# Main.net
KiCad netlist of a schematic drawn in Altium Designer
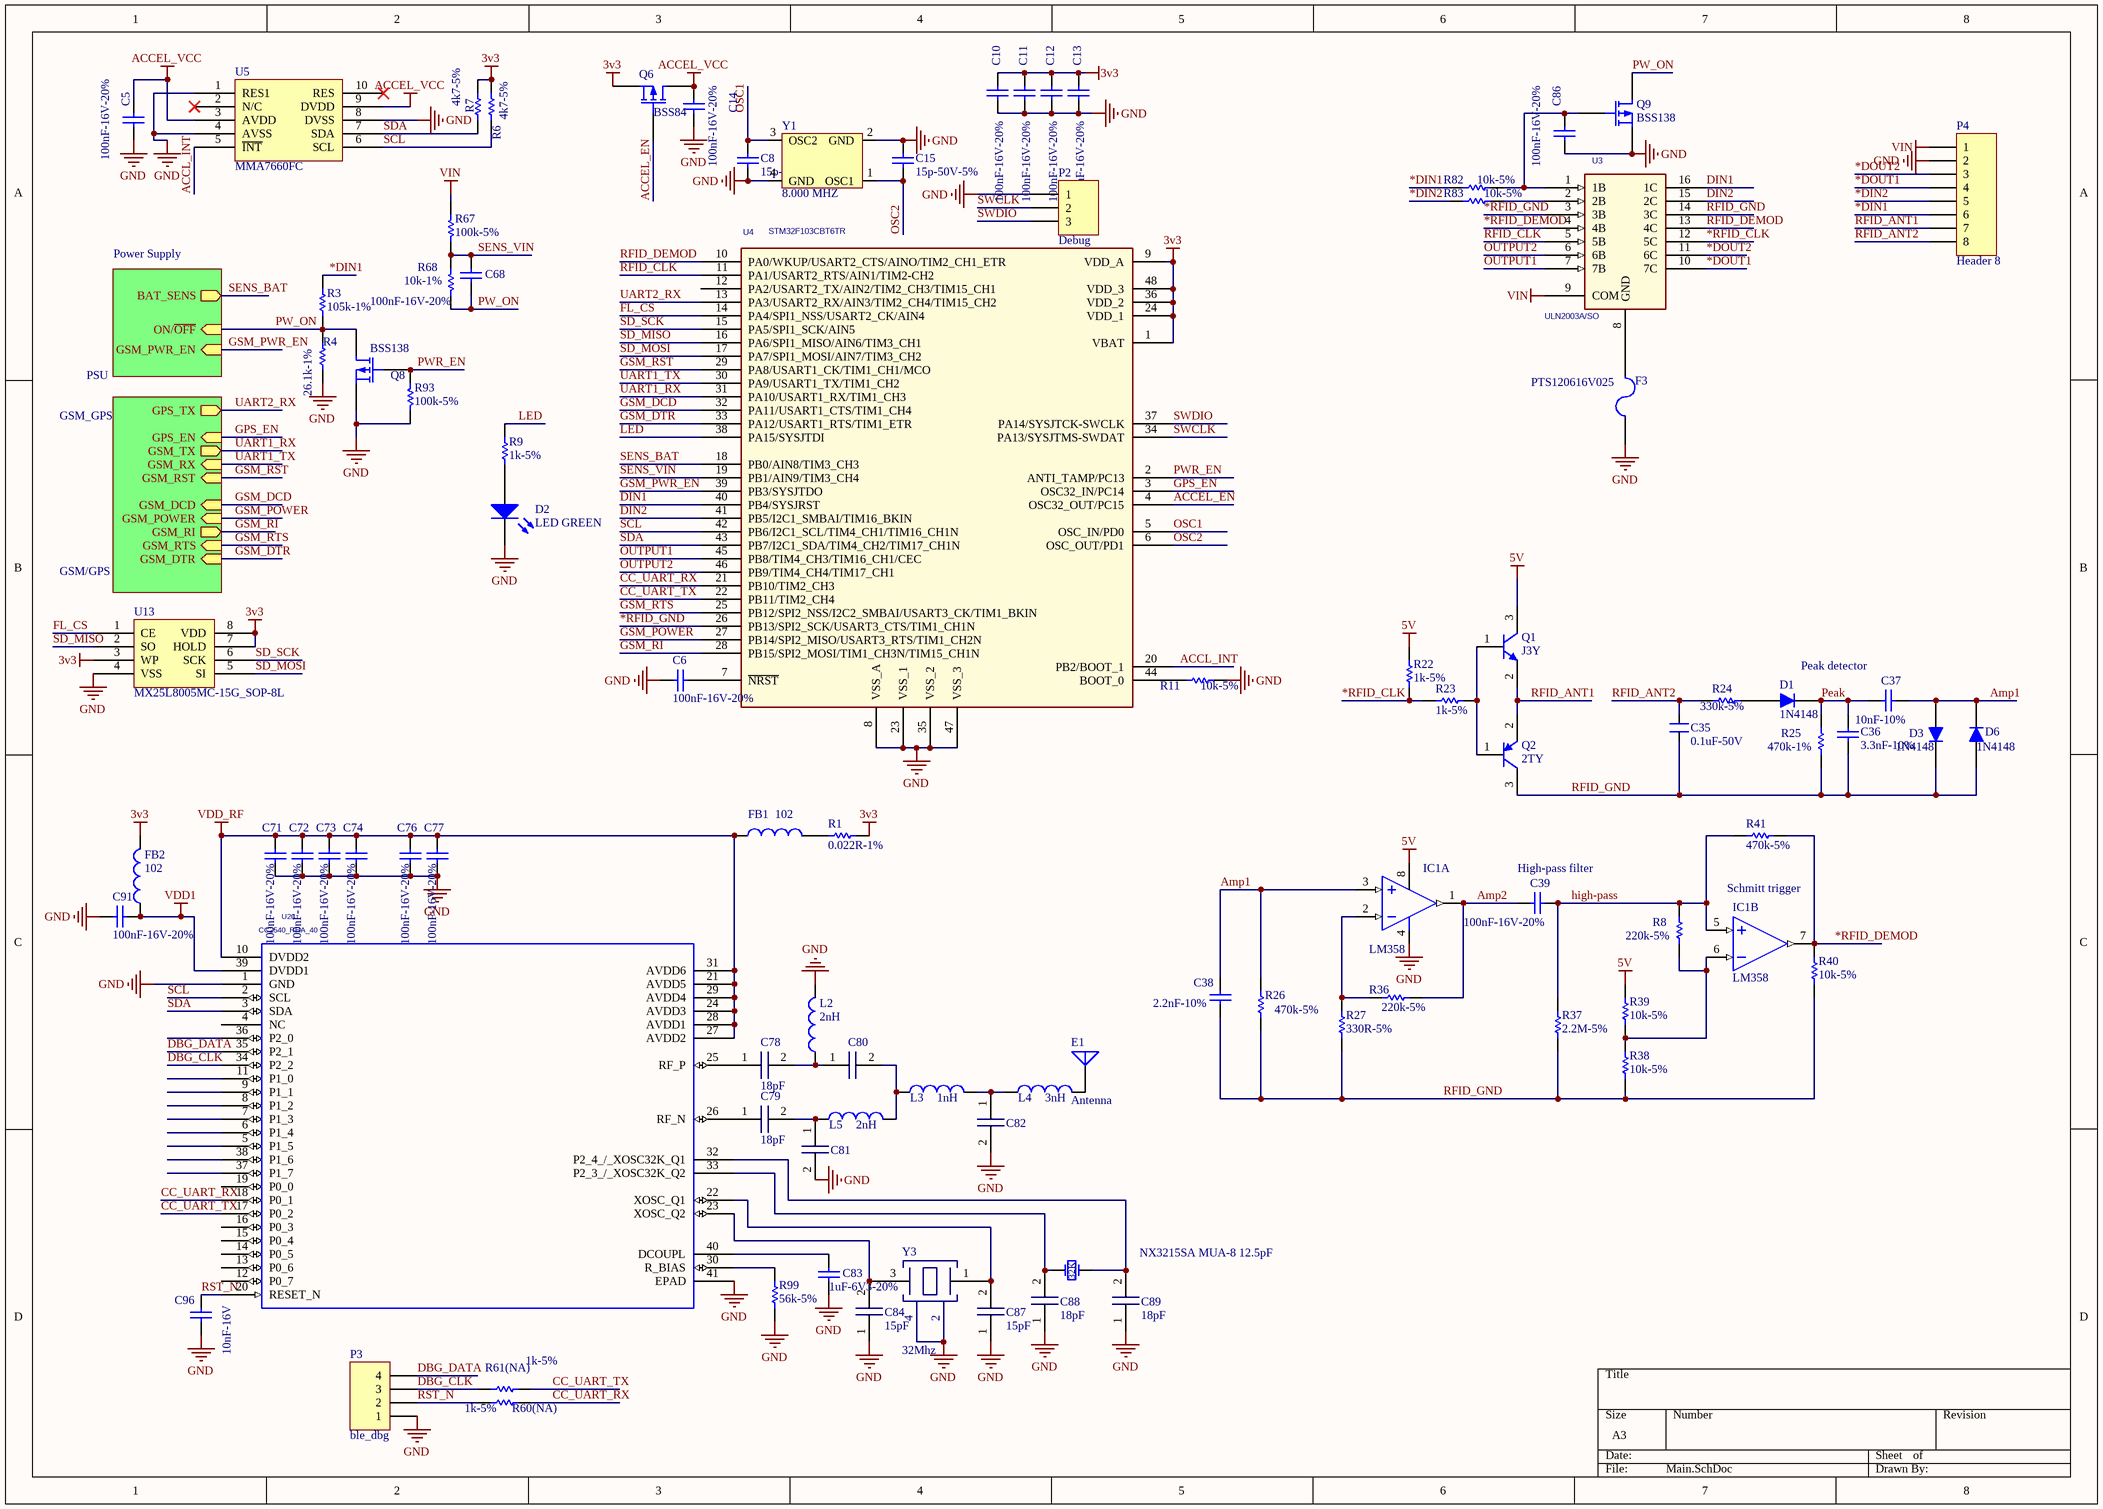
[diagram p0: Main.SchDoc]

(export (version "E")
  (design (tool "Eeschema 10.0.6"))
  (components
    (comp (ref "C5")
      (value "100nF-16V-20%")
      (footprint "C0402")
      (description "CAP CER 0.1UF 16V Y5V 0402")
      (fields
        (field (name "MANUFACTURER") "Yageo")
        (field (name "DIGI-KEY PART NUMBER") "311-1047-1-ND")
        (field (name "PUBLISHER") "Altium Limited")
      )
      (libsource (lib "Miscellaneous Devices") (part "Cap"))
    )
    (comp (ref "C6")
      (value "100nF-16V-20%")
      (footprint "C0402")
      (description "CAP CER 0.1UF 16V Y5V 0402")
      (fields
        (field (name "MANUFACTURER") "Yageo")
        (field (name "DIGI-KEY PART NUMBER") "311-1047-1-ND")
        (field (name "PUBLISHER") "Altium Limited")
      )
      (libsource (lib "Miscellaneous Devices") (part "Cap"))
    )
    (comp (ref "C8")
      (value "15p-50V-5%")
      (footprint "C0402")
      (description "CAP CER 15PF 50V 5% NPO 0402")
      (fields
        (field (name "MANUFACTURER") "Yageo")
        (field (name "DIGI-KEY PART NUMBER") "311-1017-1-ND")
        (field (name "PUBLISHER") "Altium Limited")
      )
      (libsource (lib "Miscellaneous Devices") (part "Cap"))
    )
    (comp (ref "C10")
      (value "100nF-16V-20%")
      (footprint "C0402")
      (description "CAP CER 0.1UF 16V Y5V 0402")
      (fields
        (field (name "MANUFACTURER") "Yageo")
        (field (name "DIGI-KEY PART NUMBER") "311-1047-1-ND")
        (field (name "PUBLISHER") "Altium Limited")
      )
      (libsource (lib "Miscellaneous Devices") (part "Cap"))
    )
    (comp (ref "C11")
      (value "100nF-16V-20%")
      (footprint "C0402")
      (description "CAP CER 0.1UF 16V Y5V 0402")
      (fields
        (field (name "MANUFACTURER") "Yageo")
        (field (name "DIGI-KEY PART NUMBER") "311-1047-1-ND")
        (field (name "PUBLISHER") "Altium Limited")
      )
      (libsource (lib "Miscellaneous Devices") (part "Cap"))
    )
    (comp (ref "C12")
      (value "100nF-16V-20%")
      (footprint "C0402")
      (description "CAP CER 0.1UF 16V Y5V 0402")
      (fields
        (field (name "MANUFACTURER") "Yageo")
        (field (name "DIGI-KEY PART NUMBER") "311-1047-1-ND")
        (field (name "PUBLISHER") "Altium Limited")
      )
      (libsource (lib "Miscellaneous Devices") (part "Cap"))
    )
    (comp (ref "C13")
      (value "100nF-16V-20%")
      (footprint "C0402")
      (description "CAP CER 0.1UF 16V Y5V 0402")
      (fields
        (field (name "MANUFACTURER") "Yageo")
        (field (name "DIGI-KEY PART NUMBER") "311-1047-1-ND")
        (field (name "PUBLISHER") "Altium Limited")
      )
      (libsource (lib "Miscellaneous Devices") (part "Cap"))
    )
    (comp (ref "C14")
      (value "100nF-16V-20%")
      (footprint "C0402")
      (description "CAP CER 0.1UF 16V Y5V 0402")
      (fields
        (field (name "MANUFACTURER") "Yageo")
        (field (name "DIGI-KEY PART NUMBER") "311-1047-1-ND")
        (field (name "PUBLISHER") "Altium Limited")
      )
      (libsource (lib "Miscellaneous Devices") (part "Cap"))
    )
    (comp (ref "C15")
      (value "15p-50V-5%")
      (footprint "C0402")
      (description "CAP CER 15PF 50V 5% NPO 0402")
      (fields
        (field (name "MANUFACTURER") "Yageo")
        (field (name "DIGI-KEY PART NUMBER") "311-1017-1-ND")
        (field (name "PUBLISHER") "Altium Limited")
      )
      (libsource (lib "Miscellaneous Devices") (part "Cap"))
    )
    (comp (ref "C35")
      (value "0.1uF-50V")
      (footprint "C0603")
      (description "CAP CER 0.1UF 50V Y5V 0603")
      (fields (field (name "DIGI-KEY PART NUMBER") "311-1343-2-ND") (field (name "MANUFACTURER") "Yageo"))
      (libsource (lib "syhaunguyen") (part "CN2"))
    )
    (comp (ref "C36")
      (value "3.3nF-10%")
      (footprint "C0402")
      (description "CAP CER 3300PF 50V 10% X7R 0402")
      (fields (field (name "DIGI-KEY PART NUMBER") "311-1034-2-ND") (field (name "MANUFACTURER") "Yageo"))
      (libsource (lib "Capacitor") (part "1nF-50V-C0805"))
    )
    (comp (ref "C37")
      (value "10nF-10%")
      (footprint "C0402")
      (description "Non-Polarized Capacitor")
      (fields (field (name "DIGI-KEY PART NUMBER") "CC0402KRX7R9BB103") (field (name "MANUFACTURER") "Yageo"))
      (libsource (lib "Capacitor") (part "10nF-50V-C0805"))
    )
    (comp (ref "C38")
      (value "2.2nF-10%")
      (footprint "C0402")
      (description "CAP CER 2200PF 50V 10% X7R 0402")
      (fields (field (name "DIGI-KEY PART NUMBER") "311-1037-2-ND") (field (name "MANUFACTURER") "Yageo"))
      (libsource (lib "Capacitor") (part "2.2nF-50V-C0805"))
    )
    (comp (ref "C39")
      (value "100nF-16V-20%")
      (footprint "C0402")
      (description "CAP CER 0.1UF 16V Y5V 0402")
      (fields
        (field (name "MANUFACTURER") "Yageo")
        (field (name "DIGI-KEY PART NUMBER") "311-1047-1-ND")
        (field (name "PUBLISHER") "Altium Limited")
      )
      (libsource (lib "Miscellaneous Devices") (part "Cap"))
    )
    (comp (ref "C68")
      (value "100nF-16V-20%")
      (footprint "C0402")
      (description "CAP CER 0.1UF 16V Y5V 0402")
      (fields
        (field (name "MANUFACTURER") "Yageo")
        (field (name "DIGI-KEY PART NUMBER") "311-1047-1-ND")
        (field (name "PUBLISHER") "Altium Limited")
      )
      (libsource (lib "Miscellaneous Devices") (part "Cap"))
    )
    (comp (ref "C71")
      (value "100nF-16V-20%")
      (footprint "C0402")
      (description "CAP CER 0.1UF 16V Y5V 0402")
      (fields
        (field (name "MANUFACTURER") "Yageo")
        (field (name "DIGI-KEY PART NUMBER") "311-1047-1-ND")
        (field (name "PUBLISHER") "Altium Limited")
      )
      (libsource (lib "Miscellaneous Devices") (part "Cap"))
    )
    (comp (ref "C72")
      (value "100nF-16V-20%")
      (footprint "C0402")
      (description "CAP CER 0.1UF 16V Y5V 0402")
      (fields
        (field (name "MANUFACTURER") "Yageo")
        (field (name "DIGI-KEY PART NUMBER") "311-1047-1-ND")
        (field (name "PUBLISHER") "Altium Limited")
      )
      (libsource (lib "Miscellaneous Devices") (part "Cap"))
    )
    (comp (ref "C73")
      (value "100nF-16V-20%")
      (footprint "C0402")
      (description "CAP CER 0.1UF 16V Y5V 0402")
      (fields
        (field (name "MANUFACTURER") "Yageo")
        (field (name "DIGI-KEY PART NUMBER") "311-1047-1-ND")
        (field (name "PUBLISHER") "Altium Limited")
      )
      (libsource (lib "Miscellaneous Devices") (part "Cap"))
    )
    (comp (ref "C74")
      (value "100nF-16V-20%")
      (footprint "C0402")
      (description "CAP CER 0.1UF 16V Y5V 0402")
      (fields
        (field (name "MANUFACTURER") "Yageo")
        (field (name "DIGI-KEY PART NUMBER") "311-1047-1-ND")
        (field (name "PUBLISHER") "Altium Limited")
      )
      (libsource (lib "Miscellaneous Devices") (part "Cap"))
    )
    (comp (ref "C76")
      (value "100nF-16V-20%")
      (footprint "C0402")
      (description "CAP CER 0.1UF 16V Y5V 0402")
      (fields
        (field (name "MANUFACTURER") "Yageo")
        (field (name "DIGI-KEY PART NUMBER") "311-1047-1-ND")
        (field (name "PUBLISHER") "Altium Limited")
      )
      (libsource (lib "Miscellaneous Devices") (part "Cap"))
    )
    (comp (ref "C77")
      (value "100nF-16V-20%")
      (footprint "C0402")
      (description "CAP CER 0.1UF 16V Y5V 0402")
      (fields
        (field (name "MANUFACTURER") "Yageo")
        (field (name "DIGI-KEY PART NUMBER") "311-1047-1-ND")
        (field (name "PUBLISHER") "Altium Limited")
      )
      (libsource (lib "Miscellaneous Devices") (part "Cap"))
    )
    (comp (ref "C78")
      (value "18pF")
      (footprint "C0402")
      (fields
        (field (name "MANUFACTURER") "Yageo")
        (field (name "DIGI-KEY PART NUMBER") "311-1018-1-ND")
        (field (name "MANUFACTURER PART NUMBER") "CC0402JRNPO9BN220")
      )
      (libsource (lib "Capacitor") (part "18pF"))
    )
    (comp (ref "C79")
      (value "18pF")
      (footprint "C0402")
      (fields
        (field (name "MANUFACTURER") "Yageo")
        (field (name "DIGI-KEY PART NUMBER") "311-1018-1-ND")
        (field (name "MANUFACTURER PART NUMBER") "CC0402JRNPO9BN220")
      )
      (libsource (lib "Capacitor") (part "18pF"))
    )
    (comp (ref "C80")
      (value "~")
      (footprint "C0402")
      (fields
        (field (name "DIGI-KEY PART NUMBER") "CC0402CRNPO9BN1R0-ND")
        (field (name "MANUFACTURER") "Yageo")
        (field (name "MANUFACTURER PART NUMBER") "CC0402CRNPO9BN1R0")
      )
      (libsource (lib "Capacitor") (part "1pF"))
    )
    (comp (ref "C81")
      (value "~")
      (footprint "C0402")
      (fields
        (field (name "DIGI-KEY PART NUMBER") "CC0402CRNPO9BN1R0-ND")
        (field (name "MANUFACTURER") "Yageo")
        (field (name "MANUFACTURER PART NUMBER") "CC0402CRNPO9BN1R0")
      )
      (libsource (lib "Capacitor") (part "1pF"))
    )
    (comp (ref "C82")
      (value "~")
      (footprint "C0402")
      (fields
        (field (name "DIGI-KEY PART NUMBER") "CC0402CRNPO9BN1R0-ND")
        (field (name "MANUFACTURER") "Yageo")
        (field (name "MANUFACTURER PART NUMBER") "CC0402CRNPO9BN1R0")
      )
      (libsource (lib "Capacitor") (part "1pF"))
    )
    (comp (ref "C83")
      (value "1uF-6V3-20%")
      (footprint "C0402")
      (description "CAP CER 1UF 6.3V Y5V 0402")
      (fields
        (field (name "MANUFACTURER") "Yageo")
        (field (name "DIGI-KEY PART NUMBER") "311-1377-2-ND")
        (field (name "PUBLISHER") "Altium Limited")
      )
      (libsource (lib "Miscellaneous Devices") (part "Cap"))
    )
    (comp (ref "C84")
      (value "15pF")
      (footprint "C0402")
      (fields
        (field (name "MANUFACTURER") "Yageo")
        (field (name "DIGI-KEY PART NUMBER") "311-1018-1-ND")
        (field (name "MANUFACTURER PART NUMBER") "CC0402JRNPO9BN220")
      )
      (libsource (lib "Capacitor") (part "15pF"))
    )
    (comp (ref "C86")
      (value "100nF-16V-20%")
      (footprint "C0402")
      (description "CAP CER 0.1UF 16V Y5V 0402")
      (fields
        (field (name "MANUFACTURER") "Yageo")
        (field (name "DIGI-KEY PART NUMBER") "311-1047-1-ND")
        (field (name "PUBLISHER") "Altium Limited")
      )
      (libsource (lib "Miscellaneous Devices") (part "Cap"))
    )
    (comp (ref "C87")
      (value "15pF")
      (footprint "C0402")
      (fields
        (field (name "MANUFACTURER") "Yageo")
        (field (name "DIGI-KEY PART NUMBER") "311-1018-1-ND")
        (field (name "MANUFACTURER PART NUMBER") "CC0402JRNPO9BN220")
      )
      (libsource (lib "Capacitor") (part "15pF"))
    )
    (comp (ref "C88")
      (value "18pF")
      (footprint "C0402")
      (fields
        (field (name "MANUFACTURER") "Yageo")
        (field (name "DIGI-KEY PART NUMBER") "311-1018-1-ND")
        (field (name "MANUFACTURER PART NUMBER") "CC0402JRNPO9BN220")
      )
      (libsource (lib "Capacitor") (part "18pF"))
    )
    (comp (ref "C89")
      (value "18pF")
      (footprint "C0402")
      (fields
        (field (name "MANUFACTURER") "Yageo")
        (field (name "DIGI-KEY PART NUMBER") "311-1018-1-ND")
        (field (name "MANUFACTURER PART NUMBER") "CC0402JRNPO9BN220")
      )
      (libsource (lib "Capacitor") (part "18pF"))
    )
    (comp (ref "C91")
      (value "100nF-16V-20%")
      (footprint "C0402")
      (description "CAP CER 0.1UF 16V Y5V 0402")
      (fields
        (field (name "MANUFACTURER") "Yageo")
        (field (name "DIGI-KEY PART NUMBER") "311-1047-1-ND")
        (field (name "PUBLISHER") "Altium Limited")
      )
      (libsource (lib "Miscellaneous Devices") (part "Cap"))
    )
    (comp (ref "C96")
      (value "10nF-16V")
      (footprint "C0402")
      (description "CAP CER 10000PF 16V 10% X7R 0402")
      (fields (field (name "DIGI-KEY PART NUMBER") "311-1042-2-ND") (field (name "MANUFACTURER") "Yageo"))
      (libsource (lib "Capacitor_0402") (part "10nF-16V-C0402-10%"))
    )
    (comp (ref "D1")
      (value "1N4148")
      (footprint "DO-213AA")
      (description "DIODE SMALL SIG 100V 0.2A ALF2")
      (fields
        (field (name "DIGI-KEY PART NUMBER") "568-1360-1-ND")
        (field (name "MANUFACTURER") "NXP Semiconductors")
      )
      (libsource (lib "Active Components") (part "1N4148"))
    )
    (comp (ref "D2")
      (value "LED GREEN")
      (footprint "LED0603-G")
      (description "LED GREEN CLEAR THIN 0603 SMD")
      (fields
        (field (name "DIGI-KEY PART NUMBER") "160-1446-2-ND")
        (field (name "MANUFACTURER") "Lite-On Inc")
        (field (name "PUBLISHER") "Altium Limited")
      )
      (libsource (lib "Miscellaneous Devices") (part "LED2"))
    )
    (comp (ref "D3")
      (value "1N4148")
      (footprint "DO-213AA")
      (description "DIODE SMALL SIG 100V 0.2A ALF2")
      (fields
        (field (name "DIGI-KEY PART NUMBER") "568-1360-1-ND")
        (field (name "MANUFACTURER") "NXP Semiconductors")
      )
      (libsource (lib "Active Components") (part "1N4148"))
    )
    (comp (ref "D6")
      (value "1N4148")
      (footprint "DO-213AA")
      (description "DIODE SMALL SIG 100V 0.2A ALF2")
      (fields
        (field (name "DIGI-KEY PART NUMBER") "568-1360-1-ND")
        (field (name "MANUFACTURER") "NXP Semiconductors")
      )
      (libsource (lib "Active Components") (part "1N4148"))
    )
    (comp (ref "E1")
      (value "Antenna")
      (footprint "A10192-ANTENOVA")
      (description "Generic Antenna")
      (fields (field (name "PUBLISHER") "Altium Limited"))
      (libsource (lib "Miscellaneous Devices") (part "Antenna"))
    )
    (comp (ref "F3")
      (value "PTS120616V025")
      (footprint "PTC1206")
      (description "PTC RESETTABLE SMD 1206 16V .25A")
      (fields
        (field (name "DIGI-KEY PART NUMBER") "283-3137-2-ND")
        (field (name "MANUFACTURER") "Cooper Bussmann")
        (field (name "PUBLISHER") "Altium Limited")
      )
      (libsource (lib "Miscellaneous Devices") (part "Fuse 2"))
    )
    (comp (ref "FB1")
      (value "102")
      (footprint "R0402")
      (description "Inductor")
      (fields
        (field (name "DIGI-KEY PART NUMBER") "490-1174-1-ND")
        (field (name "MANUFACTURER PART NUMBER") "LQW18AN27NJ00D")
        (field (name "PUBLISHER") "Altium Limited")
      )
      (libsource (lib "Miscellaneous Devices") (part "Inductor"))
    )
    (comp (ref "FB2")
      (value "102")
      (footprint "R0402")
      (description "Inductor")
      (fields
        (field (name "DIGI-KEY PART NUMBER") "490-1174-1-ND")
        (field (name "MANUFACTURER PART NUMBER") "LQW18AN27NJ00D")
        (field (name "PUBLISHER") "Altium Limited")
      )
      (libsource (lib "Miscellaneous Devices") (part "Inductor"))
    )
    (comp (ref "IC1")
      (value "LM358")
      (footprint "soic8")
      (description "Low-Power Dual Operational Amplifier")
      (libsource (lib "IC") (part "LM358"))
    )
    (comp (ref "L2")
      (value "2nH")
      (footprint "R0402")
      (description "Inductor")
      (fields
        (field (name "DIGI-KEY PART NUMBER") "490-1174-1-ND")
        (field (name "MANUFACTURER PART NUMBER") "LQW18AN27NJ00D")
        (field (name "PUBLISHER") "Altium Limited")
      )
      (libsource (lib "Miscellaneous Devices") (part "Inductor"))
    )
    (comp (ref "L3")
      (value "1nH")
      (footprint "R0402")
      (description "Inductor")
      (fields
        (field (name "DIGI-KEY PART NUMBER") "490-1174-1-ND")
        (field (name "MANUFACTURER PART NUMBER") "LQW18AN27NJ00D")
        (field (name "PUBLISHER") "Altium Limited")
      )
      (libsource (lib "Miscellaneous Devices") (part "Inductor"))
    )
    (comp (ref "L4")
      (value "3nH")
      (footprint "R0402")
      (description "Inductor")
      (fields
        (field (name "DIGI-KEY PART NUMBER") "490-1174-1-ND")
        (field (name "MANUFACTURER PART NUMBER") "LQW18AN27NJ00D")
        (field (name "PUBLISHER") "Altium Limited")
      )
      (libsource (lib "Miscellaneous Devices") (part "Inductor"))
    )
    (comp (ref "L5")
      (value "2nH")
      (footprint "R0402")
      (description "Inductor")
      (fields
        (field (name "DIGI-KEY PART NUMBER") "490-1174-1-ND")
        (field (name "MANUFACTURER PART NUMBER") "LQW18AN27NJ00D")
        (field (name "PUBLISHER") "Altium Limited")
      )
      (libsource (lib "Miscellaneous Devices") (part "Inductor"))
    )
    (comp (ref "P2")
      (value "Debug")
      (footprint "HEADER_1.27mm_3PIN")
      (description "NA")
      (fields (field (name "PUBLISHER") "Altium Limited"))
      (libsource (lib "Miscellaneous Connectors") (part "Header 3"))
    )
    (comp (ref "P3")
      (value "ble_dbg")
      (footprint "HEADER_1.27mm_4PIN")
      (description "Header, 4-Pin")
      (fields (field (name "PUBLISHER") "Altium Limited"))
      (libsource (lib "Miscellaneous Connectors") (part "Header 4"))
    )
    (comp (ref "P4")
      (value "Header 8")
      (footprint "HDR1X8")
      (description "Header, 8-Pin")
      (fields (field (name "PUBLISHER") "Altium Limited"))
      (libsource (lib "Miscellaneous Connectors") (part "Header 8"))
    )
    (comp (ref "Q1")
      (value "J3Y")
      (footprint "SOT23_123")
      (description "NPN Bipolar Transistor")
      (libsource (lib "Active Components") (part "NPN_123"))
    )
    (comp (ref "Q2")
      (value "2TY")
      (footprint "SOT23_123")
      (description "PNP Bipolar Transistor")
      (libsource (lib "Active Components") (part "PNP_123"))
    )
    (comp (ref "Q6")
      (value "BSS84")
      (footprint "SOT23-3")
      (description "MOSFET P-CH 50V 130MA SOT23-3")
      (fields
        (field (name "DIGI-KEY PART NUMBER") "BSS84-FDITR-ND")
        (field (name "MANUFACTURER") "Diodes Inc")
        (field (name "PUBLISHER") "Altium Limited")
      )
      (libsource (lib "") (part "MOSFET-P_1"))
    )
    (comp (ref "Q8")
      (value "BSS138")
      (footprint "SOT23-3")
      (description "MOSFET N-CH 50V 200MA SOT23-3")
      (fields
        (field (name "DIGI-KEY PART NUMBER") "BSS138-FDICT-ND")
        (field (name "MANUFACTURER") "Diodes Inc")
        (field (name "PUBLISHER") "Altium Limited")
      )
      (libsource (lib "Miscellaneous Devices") (part "MOSFET-P"))
    )
    (comp (ref "Q9")
      (value "BSS138")
      (footprint "SOT23-3")
      (description "MOSFET N-CH 50V 200MA SOT23-3")
      (fields
        (field (name "DIGI-KEY PART NUMBER") "BSS138-FDICT-ND")
        (field (name "MANUFACTURER") "Diodes Inc")
        (field (name "PUBLISHER") "Altium Limited")
      )
      (libsource (lib "Miscellaneous Devices") (part "MOSFET-P"))
    )
    (comp (ref "R1")
      (value "0.022R-1%")
      (footprint "R0402")
      (description "RES 0.022 OHM 1/4W 1% 0805 SMD")
      (fields (field (name "DIGI-KEY PART NUMBER") "311-0.022NSTR-ND") (field (name "MANUFACTURER") "Yageo"))
      (libsource (lib "All_Resistor") (part "0.022R-1%-R0805"))
    )
    (comp (ref "R3")
      (value "105k-1%")
      (footprint "R0402")
      (description "RES 105k OHM 1/4W 1% 0805 SMD")
      (fields (field (name "DIGI-KEY PART NUMBER") "311-105KCRTR-ND") (field (name "MANUFACTURER") "Yageo"))
      (libsource (lib "All_Resistor") (part "105k-1%-R0805"))
    )
    (comp (ref "R4")
      (value "26.1k-1%")
      (footprint "R0402")
      (description "RES 26.1k OHM 1/4W 1% 0805 SMD")
      (fields (field (name "DIGI-KEY PART NUMBER") "311-26.1KCRTR-ND") (field (name "MANUFACTURER") "Yageo"))
      (libsource (lib "All_Resistor") (part "26.1k-1%-R0805"))
    )
    (comp (ref "R6")
      (value "4k7-5%")
      (footprint "R0402")
      (description "RES 4.7K OHM 1/16W 5% 0402 SMD")
      (fields
        (field (name "DIGI-KEY PART NUMBER") "311-4.7KJRCT-ND")
        (field (name "MANUFACTURER") "Yageo")
        (field (name "PUBLISHER") "Altium Limited")
      )
      (libsource (lib "Miscellaneous Devices") (part "Res1"))
    )
    (comp (ref "R7")
      (value "4k7-5%")
      (footprint "R0402")
      (description "RES 4.7K OHM 1/16W 5% 0402 SMD")
      (fields
        (field (name "DIGI-KEY PART NUMBER") "311-4.7KJRCT-ND")
        (field (name "MANUFACTURER") "Yageo")
        (field (name "PUBLISHER") "Altium Limited")
      )
      (libsource (lib "Miscellaneous Devices") (part "Res1"))
    )
    (comp (ref "R8")
      (value "220k-5%")
      (footprint "R0402")
      (description "RES 220k OHM 1/8W 5% 0805 SMD")
      (fields (field (name "DIGI-KEY PART NUMBER") "311-220KARTR-ND") (field (name "MANUFACTURER") "Yageo"))
      (libsource (lib "Resistor") (part "220k-5%-R0805"))
    )
    (comp (ref "R9")
      (value "1k-5%")
      (footprint "R0402")
      (description "RES 1.0K OHM 1/16W 5% 0402 SMD")
      (fields
        (field (name "DIGI-KEY PART NUMBER") "311-1.0KJRCT-ND")
        (field (name "MANUFACTURER") "Yageo")
        (field (name "PUBLISHER") "Altium Limited")
      )
      (libsource (lib "Miscellaneous Devices") (part "Res1"))
    )
    (comp (ref "R11")
      (value "10k-5%")
      (footprint "R0402")
      (description "RES 10K OHM 1/16W 5% 0402 SMD")
      (fields
        (field (name "DIGI-KEY PART NUMBER") "311-10KJRCT-ND")
        (field (name "MANUFACTURER") "Yageo")
        (field (name "PUBLISHER") "Altium Limited")
      )
      (libsource (lib "Miscellaneous Devices") (part "Res1"))
    )
    (comp (ref "R22")
      (value "1k-5%")
      (footprint "R0402")
      (description "RES 1k OHM 1/8W 5% 0805 SMD")
      (fields (field (name "DIGI-KEY PART NUMBER") "311-1.0KARTR-ND") (field (name "MANUFACTURER") "Yageo"))
      (libsource (lib "All_Resistor") (part "1k-5%-R0805"))
    )
    (comp (ref "R23")
      (value "1k-5%")
      (footprint "R0402")
      (description "RES 1k OHM 1/8W 5% 0805 SMD")
      (fields (field (name "DIGI-KEY PART NUMBER") "311-1.0KARTR-ND") (field (name "MANUFACTURER") "Yageo"))
      (libsource (lib "All_Resistor") (part "1k-5%-R0805"))
    )
    (comp (ref "R24")
      (value "330k-5%")
      (footprint "R0402")
      (description "RES 330k OHM 1/8W 5% 0805 SMD")
      (fields (field (name "DIGI-KEY PART NUMBER") "311-330KARTR-ND") (field (name "MANUFACTURER") "Yageo"))
      (libsource (lib "Resistor") (part "330k-5%-R0805"))
    )
    (comp (ref "R25")
      (value "470k-1%")
      (footprint "R0402")
      (description "RES 470k OHM 1/4W 1% 0805 SMD")
      (fields (field (name "DIGI-KEY PART NUMBER") "311-470KCRTR-ND") (field (name "MANUFACTURER") "Yageo"))
      (libsource (lib "Resistor") (part "470k-1%-R0805"))
    )
    (comp (ref "R26")
      (value "470k-5%")
      (footprint "R0402")
      (description "RES 470k OHM 1/8W 5% 0805 SMD")
      (fields (field (name "DIGI-KEY PART NUMBER") "311-470KARTR-ND") (field (name "MANUFACTURER") "Yageo"))
      (libsource (lib "Resistor") (part "470k-5%-R0805"))
    )
    (comp (ref "R27")
      (value "330R-5%")
      (footprint "R0402")
      (description "RES 330 OHM 1/8W 5% 0805 SMD")
      (fields (field (name "DIGI-KEY PART NUMBER") "311-330ARTR-ND") (field (name "MANUFACTURER") "Yageo"))
      (libsource (lib "Resistor") (part "330R-5%-R0805"))
    )
    (comp (ref "R36")
      (value "220k-5%")
      (footprint "R0402")
      (description "RES 220k OHM 1/8W 5% 0805 SMD")
      (fields (field (name "DIGI-KEY PART NUMBER") "311-220KARTR-ND") (field (name "MANUFACTURER") "Yageo"))
      (libsource (lib "Resistor") (part "220k-5%-R0805"))
    )
    (comp (ref "R37")
      (value "2.2M-5%")
      (footprint "R0402")
      (description "RES 2.2M OHM 1/8W 5% 0805 SMD")
      (fields (field (name "DIGI-KEY PART NUMBER") "311-2.2MARTR-ND") (field (name "MANUFACTURER") "Yageo"))
      (libsource (lib "Resistor") (part "2.2M-5%-R0805"))
    )
    (comp (ref "R38")
      (value "10k-5%")
      (footprint "R0402")
      (description "RES 10k OHM 1/8W 5% 0805 SMD")
      (fields (field (name "DIGI-KEY PART NUMBER") "311-10KARTR-ND") (field (name "MANUFACTURER") "Yageo"))
      (libsource (lib "Resistor") (part "10k-5%-R0805"))
    )
    (comp (ref "R39")
      (value "10k-5%")
      (footprint "R0402")
      (description "RES 10k OHM 1/8W 5% 0805 SMD")
      (fields (field (name "DIGI-KEY PART NUMBER") "311-10KARTR-ND") (field (name "MANUFACTURER") "Yageo"))
      (libsource (lib "Resistor") (part "10k-5%-R0805"))
    )
    (comp (ref "R40")
      (value "10k-5%")
      (footprint "R0402")
      (description "RES 10k OHM 1/8W 5% 0805 SMD")
      (fields (field (name "DIGI-KEY PART NUMBER") "311-10KARTR-ND") (field (name "MANUFACTURER") "Yageo"))
      (libsource (lib "Resistor") (part "10k-5%-R0805"))
    )
    (comp (ref "R41")
      (value "470k-5%")
      (footprint "R0402")
      (description "RES 470k OHM 1/8W 5% 0805 SMD")
      (fields (field (name "DIGI-KEY PART NUMBER") "311-470KARTR-ND") (field (name "MANUFACTURER") "Yageo"))
      (libsource (lib "Resistor") (part "470k-5%-R0805"))
    )
    (comp (ref "R60(NA)")
      (value "1k-5%")
      (footprint "R0402")
      (description "RES 1.0K OHM 1/16W 5% 0402 SMD")
      (fields
        (field (name "DIGI-KEY PART NUMBER") "311-1.0KJRCT-ND")
        (field (name "MANUFACTURER") "Yageo")
        (field (name "PUBLISHER") "Altium Limited")
      )
      (libsource (lib "Miscellaneous Devices") (part "Res1"))
    )
    (comp (ref "R61(NA)")
      (value "1k-5%")
      (footprint "R0402")
      (description "RES 1.0K OHM 1/16W 5% 0402 SMD")
      (fields
        (field (name "DIGI-KEY PART NUMBER") "311-1.0KJRCT-ND")
        (field (name "MANUFACTURER") "Yageo")
        (field (name "PUBLISHER") "Altium Limited")
      )
      (libsource (lib "Miscellaneous Devices") (part "Res1"))
    )
    (comp (ref "R67")
      (value "100k-5%")
      (footprint "R0402")
      (description "RES 100K OHM 1/16W 5% 0402 SMD")
      (fields
        (field (name "DIGI-KEY PART NUMBER") "311-100KJRCT-ND")
        (field (name "MANUFACTURER") "Yageo")
        (field (name "PUBLISHER") "Altium Limited")
      )
      (libsource (lib "Miscellaneous Devices") (part "Res1"))
    )
    (comp (ref "R68")
      (value "10k-1%")
      (footprint "R0402")
      (description "RES 10.0K OHM 1/16W 1% 0402 SMD")
      (fields
        (field (name "DIGI-KEY PART NUMBER") "311-10.0KLRTR-ND")
        (field (name "MANUFACTURER") "Yageo")
        (field (name "PUBLISHER") "Altium Limited")
      )
      (libsource (lib "Miscellaneous Devices") (part "Res1"))
    )
    (comp (ref "R82")
      (value "10k-5%")
      (footprint "R0402")
      (description "RES 10K OHM 1/16W 5% 0402 SMD")
      (fields
        (field (name "DIGI-KEY PART NUMBER") "311-10KJRCT-ND")
        (field (name "MANUFACTURER") "Yageo")
        (field (name "PUBLISHER") "Altium Limited")
      )
      (libsource (lib "Miscellaneous Devices") (part "Res1"))
    )
    (comp (ref "R83")
      (value "10k-5%")
      (footprint "R0402")
      (description "RES 10K OHM 1/16W 5% 0402 SMD")
      (fields
        (field (name "DIGI-KEY PART NUMBER") "311-10KJRCT-ND")
        (field (name "MANUFACTURER") "Yageo")
        (field (name "PUBLISHER") "Altium Limited")
      )
      (libsource (lib "Miscellaneous Devices") (part "Res1"))
    )
    (comp (ref "R93")
      (value "100k-5%")
      (footprint "R0402")
      (description "RES 100K OHM 1/16W 5% 0402 SMD")
      (fields
        (field (name "DIGI-KEY PART NUMBER") "311-100KJRCT-ND")
        (field (name "MANUFACTURER") "Yageo")
        (field (name "PUBLISHER") "Altium Limited")
      )
      (libsource (lib "Miscellaneous Devices") (part "Res1"))
    )
    (comp (ref "R99")
      (value "56k-5%")
      (footprint "R0402")
      (description "RES 56k OHM 1/8W 5% 0805 SMD")
      (fields (field (name "DIGI-KEY PART NUMBER") "311-56KARTR-ND") (field (name "MANUFACTURER") "Yageo"))
      (libsource (lib "All_Resistor") (part "56k-5%-R0805"))
    )
    (comp (ref "U3")
      (value "ULN2003A/SO")
      (footprint "SO16-150mil")
      (description "IC DARL TRANS ARRAY 16-SOIC")
      (fields
        (field (name "DIGI-KEY PART NUMBER") "296-1368-2-ND")
        (field (name "MANUFACTURER PART NUMBER") "ULN2003ADR")
      )
      (libsource (lib "*") (part "ULN2003A/SO_0"))
    )
    (comp (ref "U4")
      (value "STM32F103CBT6TR")
      (footprint "TQFP-48-P0.5")
      (description "MCU ARM 128K FLASH/TIMER")
      (fields
        (field (name "DIGI-KEY PART NUMBER") "497-6288-ND")
        (field (name "MANUFACTURER") "STMicroelectronics")
      )
      (libsource (lib "*") (part "ATmega128_4"))
    )
    (comp (ref "U5")
      (value "MMA7660FC")
      (footprint "MMA7660FC")
      (description "ACCELEROMETER 3X3 DGTL 10-DFN")
      (fields
        (field (name "DIGI-KEY PART NUMBER") "MMA7660FCT-ND")
        (field (name "MANUFACTURER") "Freescale Semiconductor")
      )
      (libsource (lib "Lib") (part "MMA7660FC"))
    )
    (comp (ref "U13")
      (value "MX25L8005MC-15G_SOP-8L")
      (footprint "SO8-200mil")
      (fields (field (name "MANUFACTURER") "Tyrone"))
      (libsource (lib "My LB") (part "FlashIC"))
    )
    (comp (ref "U20")
      (value "CC2540_RHA_40")
      (footprint "CC254x")
      (description "2.4GHz Bluetooth Low Energy System-on-Chip Solution")
      (fields (field (name "MANUFACTURER") "Texas Instruments") (field (name "GENERIC_PART_NUMBER") "CC2540"))
      (libsource (lib "2013-05-06_12-03-49") (part "CC2540_RHA_40"))
    )
    (comp (ref "Y1")
      (value "8.000 MHZ")
      (footprint "SMD CRYSTAL 4 x 2.5")
      (description "CRYSTAL 8.000 MHZ 18PF SMD")
      (fields
        (field (name "DIGI-KEY PART NUMBER") "887-1452-2-ND")
        (field (name "MANUFACTURER") "TXC CORPORATION")
      )
      (libsource (lib "Schlib1") (part "CRYSTAL-SMT"))
    )
    (comp (ref "Y3")
      (value "32Mhz")
      (footprint "SMD CRYSTAL 2.5 x 2")
      (libsource (lib "msp430g2553") (part "XTAL"))
    )
    (comp (ref "Y4")
      (value "NX3215SA MUA-8 12.5pF")
      (footprint "Crystal-3.2x1.5")
      (description "Crystal Oscillator")
      (fields (field (name "PUBLISHER") "Altium Limited"))
      (libsource (lib "Schematic") (part "XTAL/32KHz"))
    )
  )
  (nets
    (net (code "1") (name "/*DIN1") (class "Default")
      (node (ref "P4") (pin "6") (pinfunction "6_6") (pintype "passive"))
      (node (ref "R3") (pin "2") (pinfunction "2_2") (pintype "passive"))
      (node (ref "R82") (pin "1") (pinfunction "1_1") (pintype "passive"))
    )
    (net (code "2") (name "/*DIN2") (class "Default")
      (node (ref "P4") (pin "5") (pinfunction "5_5") (pintype "passive"))
      (node (ref "R83") (pin "2") (pinfunction "2_2") (pintype "passive"))
    )
    (net (code "3") (name "/*DOUT1") (class "Default")
      (node (ref "P4") (pin "4") (pinfunction "4_4") (pintype "passive"))
      (node (ref "U3") (pin "10") (pinfunction "7C_10") (pintype "open_collector"))
    )
    (net (code "4") (name "/*DOUT2") (class "Default")
      (node (ref "P4") (pin "3") (pinfunction "3_3") (pintype "passive"))
      (node (ref "U3") (pin "11") (pinfunction "6C_11") (pintype "open_collector"))
    )
    (net (code "5") (name "/*RFID_CLK") (class "Default")
      (node (ref "R22") (pin "1") (pinfunction "1_1") (pintype "passive"))
      (node (ref "R23") (pin "2") (pinfunction "2_2") (pintype "passive"))
      (node (ref "U3") (pin "12") (pinfunction "5C_12") (pintype "open_collector"))
    )
    (net (code "6") (name "/*RFID_DEMOD") (class "Default")
      (node (ref "IC1") (pin "7") (pinfunction "OUT_7") (pintype "output"))
      (node (ref "R40") (pin "2") (pinfunction "2_2") (pintype "passive"))
      (node (ref "R41") (pin "1") (pinfunction "1_1") (pintype "passive"))
      (node (ref "U3") (pin "4") (pinfunction "4B_4") (pintype "input"))
    )
    (net (code "7") (name "/*RFID_GND") (class "Default")
      (node (ref "U3") (pin "3") (pinfunction "3B_3") (pintype "input"))
      (node (ref "U4") (pin "26") (pinfunction "PB13/SPI2_SCK/USART3_CTS/TIM1_CH1N_26") (pintype "passive"))
    )
    (net (code "8") (name "/ACCEL_EN") (class "Default")
      (node (ref "Q6") (pin "1") (pinfunction "G_1") (pintype "passive"))
      (node (ref "U4") (pin "4") (pinfunction "OSC32_OUT/PC15_4") (pintype "passive"))
    )
    (net (code "9") (name "/ACCL_INT") (class "Default")
      (node (ref "U4") (pin "20") (pinfunction "PB2/BOOT_1_20") (pintype "passive"))
      (node (ref "U5") (pin "5") (pinfunction "~{INT}_5") (pintype "passive"))
    )
    (net (code "10") (name "/Amp1") (class "Default")
      (node (ref "C37") (pin "2") (pinfunction "2_2") (pintype "passive"))
      (node (ref "C38") (pin "2") (pinfunction "2_2") (pintype "passive"))
      (node (ref "D3") (pin "1") (pinfunction "A_1") (pintype "passive"))
      (node (ref "D6") (pin "2") (pinfunction "K_2") (pintype "passive"))
      (node (ref "IC1") (pin "3") (pinfunction "IN+_3") (pintype "input"))
      (node (ref "R26") (pin "1") (pinfunction "1_1") (pintype "passive"))
    )
    (net (code "11") (name "/Amp2") (class "Default")
      (node (ref "C39") (pin "2") (pinfunction "2_2") (pintype "passive"))
      (node (ref "IC1") (pin "1") (pinfunction "OUT_1") (pintype "output"))
      (node (ref "R36") (pin "1") (pinfunction "1_1") (pintype "passive"))
    )
    (net (code "12") (name "/CC_UART_RX") (class "Default")
      (node (ref "R60(NA)") (pin "1") (pinfunction "1_1") (pintype "passive"))
      (node (ref "U20") (pin "18") (pinfunction "P0_1_18") (pintype "bidirectional"))
      (node (ref "U4") (pin "21") (pinfunction "PB10/TIM2_CH3_21") (pintype "passive"))
    )
    (net (code "13") (name "/CC_UART_TX") (class "Default")
      (node (ref "R61(NA)") (pin "1") (pinfunction "1_1") (pintype "passive"))
      (node (ref "U20") (pin "17") (pinfunction "P0_2_17") (pintype "bidirectional"))
      (node (ref "U4") (pin "22") (pinfunction "PB11/TIM2_CH4_22") (pintype "passive"))
    )
    (net (code "14") (name "/DBG_CLK") (class "Default")
      (node (ref "P3") (pin "3") (pinfunction "3_3") (pintype "passive"))
      (node (ref "R61(NA)") (pin "2") (pinfunction "2_2") (pintype "passive"))
      (node (ref "U20") (pin "34") (pinfunction "P2_2_34") (pintype "bidirectional"))
    )
    (net (code "15") (name "/DBG_DATA") (class "Default")
      (node (ref "P3") (pin "4") (pinfunction "4_4") (pintype "passive"))
      (node (ref "U20") (pin "35") (pinfunction "P2_1_35") (pintype "bidirectional"))
    )
    (net (code "16") (name "/DIN1") (class "Default")
      (node (ref "U3") (pin "16") (pinfunction "1C_16") (pintype "open_collector"))
      (node (ref "U4") (pin "40") (pinfunction "PB4/SYSJRST_40") (pintype "passive"))
    )
    (net (code "17") (name "/DIN2") (class "Default")
      (node (ref "U3") (pin "15") (pinfunction "2C_15") (pintype "open_collector"))
      (node (ref "U4") (pin "41") (pinfunction "PB5/I2C1_SMBAI/TIM16_BKIN_41") (pintype "passive"))
    )
    (net (code "18") (name "/FL_CS") (class "Default")
      (node (ref "U13") (pin "1") (pinfunction "CE_1") (pintype "passive"))
      (node (ref "U4") (pin "14") (pinfunction "PA4/SPI1_NSS/USART2_CK/AIN4_14") (pintype "passive"))
    )
    (net (code "19") (name "/GPS_EN") (class "Default")
      (node (ref "U4") (pin "3") (pinfunction "OSC32_IN/PC14_3") (pintype "passive"))
    )
    (net (code "20") (name "/GSM_DCD") (class "Default")
      (node (ref "U4") (pin "32") (pinfunction "PA11/USART1_CTS/TIM1_CH4_32") (pintype "passive"))
    )
    (net (code "21") (name "/GSM_DTR") (class "Default")
      (node (ref "U4") (pin "33") (pinfunction "PA12/USART1_RTS/TIM1_ETR_33") (pintype "passive"))
    )
    (net (code "22") (name "/GSM_POWER") (class "Default")
      (node (ref "U4") (pin "27") (pinfunction "PB14/SPI2_MISO/USART3_RTS/TIM1_CH2N_27") (pintype "passive"))
    )
    (net (code "23") (name "/GSM_PWR_EN") (class "Default")
      (node (ref "U4") (pin "39") (pinfunction "PB3/SYSJTDO_39") (pintype "passive"))
    )
    (net (code "24") (name "/GSM_RI") (class "Default")
      (node (ref "U4") (pin "28") (pinfunction "PB15/SPI2_MOSI/TIM1_CH3N/TIM15_CH1N_28") (pintype "passive"))
    )
    (net (code "25") (name "/GSM_RST") (class "Default")
      (node (ref "U4") (pin "29") (pinfunction "PA8/USART1_CK/TIM1_CH1/MCO_29") (pintype "passive"))
    )
    (net (code "26") (name "/GSM_RTS") (class "Default")
      (node (ref "U4") (pin "25") (pinfunction "PB12/SPI2_NSS/I2C2_SMBAI/USART3_CK/TIM1_BKIN_25") (pintype "passive"))
    )
    (net (code "27") (name "/LED") (class "Default")
      (node (ref "R9") (pin "2") (pinfunction "2_2") (pintype "passive"))
      (node (ref "U4") (pin "38") (pinfunction "PA15/SYSJTDI_38") (pintype "passive"))
    )
    (net (code "28") (name "/OSC1") (class "Default")
      (node (ref "C8") (pin "2") (pinfunction "2_2") (pintype "passive"))
      (node (ref "U4") (pin "5") (pinfunction "OSC_IN/PD0_5") (pintype "passive"))
      (node (ref "Y1") (pin "3") (pinfunction "OSC2_3") (pintype "passive"))
    )
    (net (code "29") (name "/OSC2") (class "Default")
      (node (ref "C15") (pin "1") (pinfunction "1_1") (pintype "passive"))
      (node (ref "U4") (pin "6") (pinfunction "OSC_OUT/PD1_6") (pintype "passive"))
      (node (ref "Y1") (pin "1") (pinfunction "OSC1_1") (pintype "passive"))
    )
    (net (code "30") (name "/OUTPUT1") (class "Default")
      (node (ref "U3") (pin "7") (pinfunction "7B_7") (pintype "input"))
      (node (ref "U4") (pin "45") (pinfunction "PB8/TIM4_CH3/TIM16_CH1/CEC_45") (pintype "passive"))
    )
    (net (code "31") (name "/OUTPUT2") (class "Default")
      (node (ref "U3") (pin "6") (pinfunction "6B_6") (pintype "input"))
      (node (ref "U4") (pin "46") (pinfunction "PB9/TIM4_CH4/TIM17_CH1_46") (pintype "passive"))
    )
    (net (code "32") (name "/PWR_EN") (class "Default")
      (node (ref "Q8") (pin "1") (pinfunction "G_1") (pintype "passive"))
      (node (ref "R93") (pin "1") (pinfunction "1_1") (pintype "passive"))
      (node (ref "U4") (pin "2") (pinfunction "ANTI_TAMP/PC13_2") (pintype "passive"))
    )
    (net (code "33") (name "/PW_ON") (class "Default")
      (node (ref "C68") (pin "1") (pinfunction "1_1") (pintype "passive"))
      (node (ref "Q8") (pin "3") (pinfunction "D_3") (pintype "passive"))
      (node (ref "Q9") (pin "3") (pinfunction "D_3") (pintype "passive"))
      (node (ref "R3") (pin "1") (pinfunction "1_1") (pintype "passive"))
      (node (ref "R4") (pin "2") (pinfunction "2_2") (pintype "passive"))
      (node (ref "R68") (pin "1") (pinfunction "1_1") (pintype "passive"))
    )
    (net (code "34") (name "/Peak") (class "Default")
      (node (ref "C36") (pin "1") (pinfunction "1_1") (pintype "passive"))
      (node (ref "C37") (pin "1") (pinfunction "1_1") (pintype "passive"))
      (node (ref "D1") (pin "2") (pinfunction "K_2") (pintype "passive"))
      (node (ref "R25") (pin "1") (pinfunction "1_1") (pintype "passive"))
    )
    (net (code "35") (name "/RFID_ANT1") (class "Default")
      (node (ref "P4") (pin "7") (pinfunction "7_7") (pintype "passive"))
      (node (ref "Q1") (pin "2") (pinfunction "E_2") (pintype "passive"))
      (node (ref "Q2") (pin "2") (pinfunction "E_2") (pintype "passive"))
    )
    (net (code "36") (name "/RFID_ANT2") (class "Default")
      (node (ref "C35") (pin "2") (pinfunction "2_2") (pintype "passive"))
      (node (ref "P4") (pin "8") (pinfunction "8_8") (pintype "passive"))
      (node (ref "R24") (pin "2") (pinfunction "2_2") (pintype "passive"))
    )
    (net (code "37") (name "/RFID_CLK") (class "Default")
      (node (ref "U3") (pin "5") (pinfunction "5B_5") (pintype "input"))
      (node (ref "U4") (pin "11") (pinfunction "PA1/USART2_RTS/AIN1/TIM2-CH2_11") (pintype "passive"))
    )
    (net (code "38") (name "/RFID_DEMOD") (class "Default")
      (node (ref "U3") (pin "13") (pinfunction "4C_13") (pintype "open_collector"))
      (node (ref "U4") (pin "10") (pinfunction "PA0/WKUP/USART2_CTS/AINO/TIM2_CH1_ETR_10") (pintype "passive"))
    )
    (net (code "39") (name "/RFID_GND") (class "Default")
      (node (ref "C35") (pin "1") (pinfunction "1_1") (pintype "passive"))
      (node (ref "C36") (pin "2") (pinfunction "2_2") (pintype "passive"))
      (node (ref "C38") (pin "1") (pinfunction "1_1") (pintype "passive"))
      (node (ref "D3") (pin "2") (pinfunction "K_2") (pintype "passive"))
      (node (ref "D6") (pin "1") (pinfunction "A_1") (pintype "passive"))
      (node (ref "Q2") (pin "3") (pinfunction "C_3") (pintype "passive"))
      (node (ref "R25") (pin "2") (pinfunction "2_2") (pintype "passive"))
      (node (ref "R26") (pin "2") (pinfunction "2_2") (pintype "passive"))
      (node (ref "R27") (pin "1") (pinfunction "1_1") (pintype "passive"))
      (node (ref "R37") (pin "1") (pinfunction "1_1") (pintype "passive"))
      (node (ref "R38") (pin "2") (pinfunction "2_2") (pintype "passive"))
      (node (ref "R40") (pin "1") (pinfunction "1_1") (pintype "passive"))
      (node (ref "U3") (pin "14") (pinfunction "3C_14") (pintype "open_collector"))
    )
    (net (code "40") (name "/RST_N") (class "Default")
      (node (ref "C96") (pin "2") (pinfunction "2_2") (pintype "passive"))
      (node (ref "P3") (pin "2") (pinfunction "2_2") (pintype "passive"))
      (node (ref "R60(NA)") (pin "2") (pinfunction "2_2") (pintype "passive"))
      (node (ref "U20") (pin "20") (pinfunction "RESET_N_20") (pintype "input"))
    )
    (net (code "41") (name "/SCL") (class "Default")
      (node (ref "R6") (pin "1") (pinfunction "1_1") (pintype "passive"))
      (node (ref "U20") (pin "2") (pinfunction "SCL_2") (pintype "bidirectional"))
      (node (ref "U4") (pin "42") (pinfunction "PB6/I2C1_SCL/TIM4_CH1/TIM16_CH1N_42") (pintype "passive"))
      (node (ref "U5") (pin "6") (pinfunction "SCL_6") (pintype "passive"))
    )
    (net (code "42") (name "/SDA") (class "Default")
      (node (ref "R7") (pin "1") (pinfunction "1_1") (pintype "passive"))
      (node (ref "U20") (pin "3") (pinfunction "SDA_3") (pintype "bidirectional"))
      (node (ref "U4") (pin "43") (pinfunction "PB7/I2C1_SDA/TIM4_CH2/TIM17_CH1N_43") (pintype "passive"))
      (node (ref "U5") (pin "7") (pinfunction "SDA_7") (pintype "passive"))
    )
    (net (code "43") (name "/SD_MISO") (class "Default")
      (node (ref "U13") (pin "2") (pinfunction "SO_2") (pintype "passive"))
      (node (ref "U4") (pin "16") (pinfunction "PA6/SPI1_MISO/AIN6/TIM3_CH1_16") (pintype "passive"))
    )
    (net (code "44") (name "/SD_MOSI") (class "Default")
      (node (ref "U13") (pin "5") (pinfunction "SI_5") (pintype "passive"))
      (node (ref "U4") (pin "17") (pinfunction "PA7/SPI1_MOSI/AIN7/TIM3_CH2_17") (pintype "passive"))
    )
    (net (code "45") (name "/SD_SCK") (class "Default")
      (node (ref "U13") (pin "6") (pinfunction "SCK_6") (pintype "passive"))
      (node (ref "U4") (pin "15") (pinfunction "PA5/SPI1_SCK/AIN5_15") (pintype "passive"))
    )
    (net (code "46") (name "/SENS_BAT") (class "Default")
      (node (ref "U4") (pin "18") (pinfunction "PB0/AIN8/TIM3_CH3_18") (pintype "passive"))
    )
    (net (code "47") (name "/SENS_VIN") (class "Default")
      (node (ref "C68") (pin "2") (pinfunction "2_2") (pintype "passive"))
      (node (ref "R67") (pin "2") (pinfunction "2_2") (pintype "passive"))
      (node (ref "R68") (pin "2") (pinfunction "2_2") (pintype "passive"))
      (node (ref "U4") (pin "19") (pinfunction "PB1/AIN9/TIM3_CH4_19") (pintype "passive"))
    )
    (net (code "48") (name "/SWCLK") (class "Default")
      (node (ref "P2") (pin "2") (pinfunction "2_2") (pintype "passive"))
      (node (ref "U4") (pin "34") (pinfunction "PA13/SYSJTMS-SWDAT_34") (pintype "passive"))
    )
    (net (code "49") (name "/SWDIO") (class "Default")
      (node (ref "P2") (pin "3") (pinfunction "3_3") (pintype "passive"))
      (node (ref "U4") (pin "37") (pinfunction "PA14/SYSJTCK-SWCLK_37") (pintype "passive"))
    )
    (net (code "50") (name "/UART1_RX") (class "Default")
      (node (ref "U4") (pin "31") (pinfunction "PA10/USART1_RX/TIM1_CH3_31") (pintype "passive"))
    )
    (net (code "51") (name "/UART1_TX") (class "Default")
      (node (ref "U4") (pin "30") (pinfunction "PA9/USART1_TX/TIM1_CH2_30") (pintype "passive"))
    )
    (net (code "52") (name "/UART2_RX") (class "Default")
      (node (ref "U4") (pin "13") (pinfunction "PA3/USART2_RX/AIN3/TIM2_CH4/TIM15_CH2_13") (pintype "passive"))
    )
    (net (code "53") (name "/high-pass") (class "Default")
      (node (ref "C39") (pin "1") (pinfunction "1_1") (pintype "passive"))
      (node (ref "IC1") (pin "5") (pinfunction "IN+_5") (pintype "input"))
      (node (ref "R37") (pin "2") (pinfunction "2_2") (pintype "passive"))
      (node (ref "R41") (pin "2") (pinfunction "2_2") (pintype "passive"))
      (node (ref "R8") (pin "2") (pinfunction "2_2") (pintype "passive"))
    )
    (net (code "54") (name "3v3") (class "Default")
      (node (ref "C10") (pin "1") (pinfunction "1_1") (pintype "passive"))
      (node (ref "C11") (pin "1") (pinfunction "1_1") (pintype "passive"))
      (node (ref "C12") (pin "1") (pinfunction "1_1") (pintype "passive"))
      (node (ref "C13") (pin "1") (pinfunction "1_1") (pintype "passive"))
      (node (ref "FB2") (pin "2") (pinfunction "2_2") (pintype "passive"))
      (node (ref "Q6") (pin "2") (pinfunction "S_2") (pintype "passive"))
      (node (ref "R1") (pin "2") (pinfunction "2_2") (pintype "passive"))
      (node (ref "R6") (pin "2") (pinfunction "2_2") (pintype "passive"))
      (node (ref "R7") (pin "2") (pinfunction "2_2") (pintype "passive"))
      (node (ref "U13") (pin "3") (pinfunction "WP_3") (pintype "passive"))
      (node (ref "U13") (pin "7") (pinfunction "HOLD_7") (pintype "passive"))
      (node (ref "U13") (pin "8") (pinfunction "VDD_8") (pintype "passive"))
      (node (ref "U4") (pin "1") (pinfunction "VBAT_1") (pintype "passive"))
      (node (ref "U4") (pin "24") (pinfunction "VDD_1_24") (pintype "passive"))
      (node (ref "U4") (pin "36") (pinfunction "VDD_2_36") (pintype "passive"))
      (node (ref "U4") (pin "48") (pinfunction "VDD_3_48") (pintype "passive"))
      (node (ref "U4") (pin "9") (pinfunction "VDD_A_9") (pintype "passive"))
    )
    (net (code "55") (name "5V") (class "Default")
      (node (ref "IC1") (pin "8") (pinfunction "+V_8") (pintype "passive"))
      (node (ref "Q1") (pin "3") (pinfunction "C_3") (pintype "passive"))
      (node (ref "R22") (pin "2") (pinfunction "2_2") (pintype "passive"))
      (node (ref "R39") (pin "1") (pinfunction "1_1") (pintype "passive"))
    )
    (net (code "56") (name "ACCEL_VCC") (class "Default")
      (node (ref "C14") (pin "2") (pinfunction "2_2") (pintype "passive"))
      (node (ref "C5") (pin "2") (pinfunction "2_2") (pintype "passive"))
      (node (ref "Q6") (pin "3") (pinfunction "D_3") (pintype "passive"))
      (node (ref "U5") (pin "3") (pinfunction "AVDD_3") (pintype "passive"))
      (node (ref "U5") (pin "9") (pinfunction "DVDD_9") (pintype "passive"))
    )
    (net (code "57") (name "GND") (class "Default")
      (node (ref "C10") (pin "2") (pinfunction "2_2") (pintype "passive"))
      (node (ref "C11") (pin "2") (pinfunction "2_2") (pintype "passive"))
      (node (ref "C12") (pin "2") (pinfunction "2_2") (pintype "passive"))
      (node (ref "C13") (pin "2") (pinfunction "2_2") (pintype "passive"))
      (node (ref "C14") (pin "1") (pinfunction "1_1") (pintype "passive"))
      (node (ref "C15") (pin "2") (pinfunction "2_2") (pintype "passive"))
      (node (ref "C5") (pin "1") (pinfunction "1_1") (pintype "passive"))
      (node (ref "C6") (pin "2") (pinfunction "2_2") (pintype "passive"))
      (node (ref "C71") (pin "2") (pinfunction "2_2") (pintype "passive"))
      (node (ref "C72") (pin "2") (pinfunction "2_2") (pintype "passive"))
      (node (ref "C73") (pin "2") (pinfunction "2_2") (pintype "passive"))
      (node (ref "C74") (pin "2") (pinfunction "2_2") (pintype "passive"))
      (node (ref "C76") (pin "2") (pinfunction "2_2") (pintype "passive"))
      (node (ref "C77") (pin "2") (pinfunction "2_2") (pintype "passive"))
      (node (ref "C8") (pin "1") (pinfunction "1_1") (pintype "passive"))
      (node (ref "C81") (pin "2") (pinfunction "2_2") (pintype "passive"))
      (node (ref "C82") (pin "2") (pinfunction "2_2") (pintype "passive"))
      (node (ref "C83") (pin "2") (pinfunction "2_2") (pintype "passive"))
      (node (ref "C84") (pin "1") (pinfunction "1_1") (pintype "passive"))
      (node (ref "C86") (pin "1") (pinfunction "1_1") (pintype "passive"))
      (node (ref "C87") (pin "1") (pinfunction "1_1") (pintype "passive"))
      (node (ref "C88") (pin "1") (pinfunction "1_1") (pintype "passive"))
      (node (ref "C89") (pin "1") (pinfunction "1_1") (pintype "passive"))
      (node (ref "C91") (pin "1") (pinfunction "1_1") (pintype "passive"))
      (node (ref "C96") (pin "1") (pinfunction "1_1") (pintype "passive"))
      (node (ref "D2") (pin "2") (pinfunction "K_2") (pintype "passive"))
      (node (ref "F3") (pin "2") (pinfunction "2_2") (pintype "passive"))
      (node (ref "IC1") (pin "4") (pinfunction "-V_4") (pintype "passive"))
      (node (ref "L2") (pin "2") (pinfunction "2_2") (pintype "passive"))
      (node (ref "P2") (pin "1") (pinfunction "1_1") (pintype "passive"))
      (node (ref "P3") (pin "1") (pinfunction "1_1") (pintype "passive"))
      (node (ref "P4") (pin "2") (pinfunction "2_2") (pintype "passive"))
      (node (ref "Q8") (pin "2") (pinfunction "S_2") (pintype "passive"))
      (node (ref "Q9") (pin "2") (pinfunction "S_2") (pintype "passive"))
      (node (ref "R11") (pin "1") (pinfunction "1_1") (pintype "passive"))
      (node (ref "R4") (pin "1") (pinfunction "1_1") (pintype "passive"))
      (node (ref "R93") (pin "2") (pinfunction "2_2") (pintype "passive"))
      (node (ref "R99") (pin "1") (pinfunction "1_1") (pintype "passive"))
      (node (ref "U13") (pin "4") (pinfunction "VSS_4") (pintype "passive"))
      (node (ref "U20") (pin "1") (pinfunction "GND_1") (pintype "power_in"))
      (node (ref "U20") (pin "41") (pinfunction "EPAD_41") (pintype "power_in"))
      (node (ref "U4") (pin "23") (pinfunction "VSS_1_23") (pintype "passive"))
      (node (ref "U4") (pin "35") (pinfunction "VSS_2_35") (pintype "passive"))
      (node (ref "U4") (pin "47") (pinfunction "VSS_3_47") (pintype "passive"))
      (node (ref "U4") (pin "8") (pinfunction "VSS_A_8") (pintype "passive"))
      (node (ref "U5") (pin "1") (pinfunction "RES1_1") (pintype "passive"))
      (node (ref "U5") (pin "4") (pinfunction "AVSS_4") (pintype "passive"))
      (node (ref "U5") (pin "8") (pinfunction "DVSS_8") (pintype "passive"))
      (node (ref "Y1") (pin "2") (pinfunction "GND_2") (pintype "passive"))
      (node (ref "Y1") (pin "4") (pinfunction "GND_4") (pintype "passive"))
      (node (ref "Y3") (pin "2") (pinfunction "6_2") (pintype "passive"))
      (node (ref "Y3") (pin "4") (pinfunction "4_4") (pintype "passive"))
    )
    (net (code "58") (name "Net-(C78-Pad2)") (class "Default")
      (node (ref "C78") (pin "2") (pinfunction "2_2") (pintype "passive"))
      (node (ref "C80") (pin "1") (pinfunction "1_1") (pintype "passive"))
      (node (ref "L2") (pin "1") (pinfunction "1_1") (pintype "passive"))
    )
    (net (code "59") (name "Net-(C79-Pad2)") (class "Default")
      (node (ref "C79") (pin "2") (pinfunction "2_2") (pintype "passive"))
      (node (ref "C81") (pin "1") (pinfunction "1_1") (pintype "passive"))
      (node (ref "L5") (pin "1") (pinfunction "1_1") (pintype "passive"))
    )
    (net (code "60") (name "Net-(C80-Pad2)") (class "Default")
      (node (ref "C80") (pin "2") (pinfunction "2_2") (pintype "passive"))
      (node (ref "L3") (pin "1") (pinfunction "1_1") (pintype "passive"))
      (node (ref "L5") (pin "2") (pinfunction "2_2") (pintype "passive"))
    )
    (net (code "61") (name "Net-(C82-Pad1)") (class "Default")
      (node (ref "C82") (pin "1") (pinfunction "1_1") (pintype "passive"))
      (node (ref "L3") (pin "2") (pinfunction "2_2") (pintype "passive"))
      (node (ref "L4") (pin "1") (pinfunction "1_1") (pintype "passive"))
    )
    (net (code "62") (name "Net-(D1-A)") (class "Default")
      (node (ref "D1") (pin "1") (pinfunction "A_1") (pintype "passive"))
      (node (ref "R24") (pin "1") (pinfunction "1_1") (pintype "passive"))
    )
    (net (code "63") (name "Net-(D2-A)") (class "Default")
      (node (ref "D2") (pin "1") (pinfunction "A_1") (pintype "passive"))
      (node (ref "R9") (pin "1") (pinfunction "1_1") (pintype "passive"))
    )
    (net (code "64") (name "Net-(E1-A)") (class "Default")
      (node (ref "E1") (pin "1") (pinfunction "A_1") (pintype "passive"))
      (node (ref "L4") (pin "2") (pinfunction "2_2") (pintype "passive"))
    )
    (net (code "65") (name "Net-(FB1-Pad2)") (class "Default")
      (node (ref "FB1") (pin "2") (pinfunction "2_2") (pintype "passive"))
      (node (ref "R1") (pin "1") (pinfunction "1_1") (pintype "passive"))
    )
    (net (code "66") (name "Net-(IC1A-IN-)") (class "Default")
      (node (ref "IC1") (pin "2") (pinfunction "IN-_2") (pintype "input"))
      (node (ref "R27") (pin "2") (pinfunction "2_2") (pintype "passive"))
      (node (ref "R36") (pin "2") (pinfunction "2_2") (pintype "passive"))
    )
    (net (code "67") (name "Net-(IC1B-IN-)") (class "Default")
      (node (ref "IC1") (pin "6") (pinfunction "IN-_6") (pintype "input"))
      (node (ref "R38") (pin "1") (pinfunction "1_1") (pintype "passive"))
      (node (ref "R39") (pin "2") (pinfunction "2_2") (pintype "passive"))
      (node (ref "R8") (pin "1") (pinfunction "1_1") (pintype "passive"))
    )
    (net (code "68") (name "Net-(Q1-B)") (class "Default")
      (node (ref "Q1") (pin "1") (pinfunction "B_1") (pintype "passive"))
      (node (ref "Q2") (pin "1") (pinfunction "B_1") (pintype "passive"))
      (node (ref "R23") (pin "1") (pinfunction "1_1") (pintype "passive"))
    )
    (net (code "69") (name "Net-(Q9-G)") (class "Default")
      (node (ref "C86") (pin "2") (pinfunction "2_2") (pintype "passive"))
      (node (ref "Q9") (pin "1") (pinfunction "G_1") (pintype "passive"))
      (node (ref "R82") (pin "2") (pinfunction "2_2") (pintype "passive"))
      (node (ref "U3") (pin "1") (pinfunction "1B_1") (pintype "input"))
    )
    (net (code "70") (name "Net-(U3-2B)") (class "Default")
      (node (ref "R83") (pin "1") (pinfunction "1_1") (pintype "passive"))
      (node (ref "U3") (pin "2") (pinfunction "2B_2") (pintype "input"))
    )
    (net (code "71") (name "Net-(U3-GND)") (class "Default")
      (node (ref "F3") (pin "1") (pinfunction "1_1") (pintype "passive"))
      (node (ref "U3") (pin "8") (pinfunction "GND_8") (pintype "power_in"))
    )
    (net (code "72") (name "Net-(U4-BOOT_0)") (class "Default")
      (node (ref "R11") (pin "2") (pinfunction "2_2") (pintype "passive"))
      (node (ref "U4") (pin "44") (pinfunction "BOOT_0_44") (pintype "passive"))
    )
    (net (code "73") (name "Net-(U4-~{NRST})") (class "Default")
      (node (ref "C6") (pin "1") (pinfunction "1_1") (pintype "passive"))
      (node (ref "U4") (pin "7") (pinfunction "~{NRST}_7") (pintype "passive"))
    )
    (net (code "74") (name "Net-(U20-DCOUPL)") (class "Default")
      (node (ref "C83") (pin "1") (pinfunction "1_1") (pintype "passive"))
      (node (ref "U20") (pin "40") (pinfunction "DCOUPL_40") (pintype "power_in"))
    )
    (net (code "75") (name "Net-(U20-P2_3_{slash}_XOSC32K_Q2)") (class "Default")
      (node (ref "C88") (pin "2") (pinfunction "2_2") (pintype "passive"))
      (node (ref "U20") (pin "33") (pinfunction "P2_3_/_XOSC32K_Q2_33") (pintype "passive"))
      (node (ref "Y4") (pin "1") (pinfunction "OSC1_1") (pintype "passive"))
    )
    (net (code "76") (name "Net-(U20-P2_4_{slash}_XOSC32K_Q1)") (class "Default")
      (node (ref "C89") (pin "2") (pinfunction "2_2") (pintype "passive"))
      (node (ref "U20") (pin "32") (pinfunction "P2_4_/_XOSC32K_Q1_32") (pintype "passive"))
      (node (ref "Y4") (pin "2") (pinfunction "OSC2_2") (pintype "passive"))
    )
    (net (code "77") (name "Net-(U20-RF_N)") (class "Default")
      (node (ref "C79") (pin "1") (pinfunction "1_1") (pintype "passive"))
      (node (ref "U20") (pin "26") (pinfunction "RF_N_26") (pintype "bidirectional"))
    )
    (net (code "78") (name "Net-(U20-RF_P)") (class "Default")
      (node (ref "C78") (pin "1") (pinfunction "1_1") (pintype "passive"))
      (node (ref "U20") (pin "25") (pinfunction "RF_P_25") (pintype "bidirectional"))
    )
    (net (code "79") (name "Net-(U20-R_BIAS)") (class "Default")
      (node (ref "R99") (pin "2") (pinfunction "2_2") (pintype "passive"))
      (node (ref "U20") (pin "30") (pinfunction "R_BIAS_30") (pintype "bidirectional"))
    )
    (net (code "80") (name "Net-(U20-XOSC_Q1)") (class "Default")
      (node (ref "C87") (pin "2") (pinfunction "2_2") (pintype "passive"))
      (node (ref "U20") (pin "22") (pinfunction "XOSC_Q1_22") (pintype "bidirectional"))
      (node (ref "Y3") (pin "1") (pintype "passive"))
    )
    (net (code "81") (name "Net-(U20-XOSC_Q2)") (class "Default")
      (node (ref "C84") (pin "2") (pinfunction "2_2") (pintype "passive"))
      (node (ref "U20") (pin "23") (pinfunction "XOSC_Q2_23") (pintype "bidirectional"))
      (node (ref "Y3") (pin "3") (pinfunction "1_3") (pintype "passive"))
    )
    (net (code "82") (name "VDD1") (class "Default")
      (node (ref "C91") (pin "2") (pinfunction "2_2") (pintype "passive"))
      (node (ref "FB2") (pin "1") (pinfunction "1_1") (pintype "passive"))
      (node (ref "U20") (pin "39") (pinfunction "DVDD1_39") (pintype "power_in"))
    )
    (net (code "83") (name "VDD_RF") (class "Default")
      (node (ref "C71") (pin "1") (pinfunction "1_1") (pintype "passive"))
      (node (ref "C72") (pin "1") (pinfunction "1_1") (pintype "passive"))
      (node (ref "C73") (pin "1") (pinfunction "1_1") (pintype "passive"))
      (node (ref "C74") (pin "1") (pinfunction "1_1") (pintype "passive"))
      (node (ref "C76") (pin "1") (pinfunction "1_1") (pintype "passive"))
      (node (ref "C77") (pin "1") (pinfunction "1_1") (pintype "passive"))
      (node (ref "FB1") (pin "1") (pinfunction "1_1") (pintype "passive"))
      (node (ref "U20") (pin "10") (pinfunction "DVDD2_10") (pintype "power_in"))
      (node (ref "U20") (pin "21") (pinfunction "AVDD5_21") (pintype "power_in"))
      (node (ref "U20") (pin "24") (pinfunction "AVDD3_24") (pintype "power_in"))
      (node (ref "U20") (pin "27") (pinfunction "AVDD2_27") (pintype "power_in"))
      (node (ref "U20") (pin "28") (pinfunction "AVDD1_28") (pintype "power_in"))
      (node (ref "U20") (pin "29") (pinfunction "AVDD4_29") (pintype "power_in"))
      (node (ref "U20") (pin "31") (pinfunction "AVDD6_31") (pintype "power_in"))
    )
    (net (code "84") (name "VIN") (class "Default")
      (node (ref "P4") (pin "1") (pinfunction "1_1") (pintype "passive"))
      (node (ref "R67") (pin "1") (pinfunction "1_1") (pintype "passive"))
      (node (ref "U3") (pin "9") (pinfunction "COM_9") (pintype "passive"))
    )
    (net (code "85") (name "unconnected-(U4-PA2{slash}USART2_TX{slash}AIN2{slash}TIM2_CH3{slash}TIM15_CH1-Pad12)") (class "Default")
      (node (ref "U4") (pin "12") (pinfunction "PA2/USART2_TX/AIN2/TIM2_CH3/TIM15_CH1_12") (pintype "passive"))
    )
    (net (code "86") (name "unconnected-(U5-N{slash}C-Pad2)") (class "Default")
      (node (ref "U5") (pin "2") (pinfunction "N/C_2") (pintype "passive+no_connect"))
    )
    (net (code "87") (name "unconnected-(U5-RES-Pad10)") (class "Default")
      (node (ref "U5") (pin "10") (pinfunction "RES_10") (pintype "passive+no_connect"))
    )
    (net (code "88") (name "unconnected-(U20-NC-Pad4)") (class "Default")
      (node (ref "U20") (pin "4") (pinfunction "NC_4") (pintype "power_in"))
    )
    (net (code "89") (name "unconnected-(U20-P0_0-Pad19)") (class "Default")
      (node (ref "U20") (pin "19") (pinfunction "P0_0_19") (pintype "bidirectional"))
    )
    (net (code "90") (name "unconnected-(U20-P0_3-Pad16)") (class "Default")
      (node (ref "U20") (pin "16") (pinfunction "P0_3_16") (pintype "bidirectional"))
    )
    (net (code "91") (name "unconnected-(U20-P0_4-Pad15)") (class "Default")
      (node (ref "U20") (pin "15") (pinfunction "P0_4_15") (pintype "bidirectional"))
    )
    (net (code "92") (name "unconnected-(U20-P0_5-Pad14)") (class "Default")
      (node (ref "U20") (pin "14") (pinfunction "P0_5_14") (pintype "bidirectional"))
    )
    (net (code "93") (name "unconnected-(U20-P0_6-Pad13)") (class "Default")
      (node (ref "U20") (pin "13") (pinfunction "P0_6_13") (pintype "bidirectional"))
    )
    (net (code "94") (name "unconnected-(U20-P0_7-Pad12)") (class "Default")
      (node (ref "U20") (pin "12") (pinfunction "P0_7_12") (pintype "bidirectional"))
    )
    (net (code "95") (name "unconnected-(U20-P1_0-Pad11)") (class "Default")
      (node (ref "U20") (pin "11") (pinfunction "P1_0_11") (pintype "bidirectional"))
    )
    (net (code "96") (name "unconnected-(U20-P1_1-Pad9)") (class "Default")
      (node (ref "U20") (pin "9") (pinfunction "P1_1_9") (pintype "bidirectional"))
    )
    (net (code "97") (name "unconnected-(U20-P1_2-Pad8)") (class "Default")
      (node (ref "U20") (pin "8") (pinfunction "P1_2_8") (pintype "bidirectional"))
    )
    (net (code "98") (name "unconnected-(U20-P1_3-Pad7)") (class "Default")
      (node (ref "U20") (pin "7") (pinfunction "P1_3_7") (pintype "bidirectional"))
    )
    (net (code "99") (name "unconnected-(U20-P1_4-Pad6)") (class "Default")
      (node (ref "U20") (pin "6") (pinfunction "P1_4_6") (pintype "bidirectional"))
    )
    (net (code "100") (name "unconnected-(U20-P1_5-Pad5)") (class "Default")
      (node (ref "U20") (pin "5") (pinfunction "P1_5_5") (pintype "bidirectional"))
    )
    (net (code "101") (name "unconnected-(U20-P1_6-Pad38)") (class "Default")
      (node (ref "U20") (pin "38") (pinfunction "P1_6_38") (pintype "bidirectional"))
    )
    (net (code "102") (name "unconnected-(U20-P1_7-Pad37)") (class "Default")
      (node (ref "U20") (pin "37") (pinfunction "P1_7_37") (pintype "bidirectional"))
    )
    (net (code "103") (name "unconnected-(U20-P2_0-Pad36)") (class "Default")
      (node (ref "U20") (pin "36") (pinfunction "P2_0_36") (pintype "bidirectional"))
    )
  )
)
